# POWER.net
KiCad netlist of a schematic drawn in Altium Designer
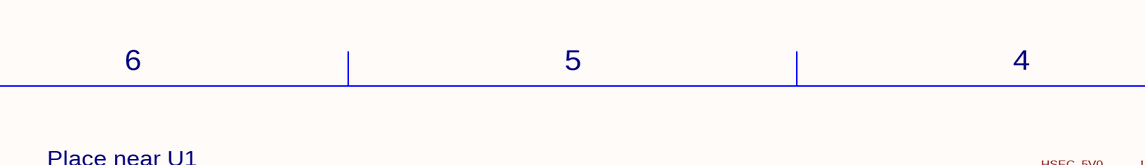
[diagram p0: POWER.SchDoc, top left]
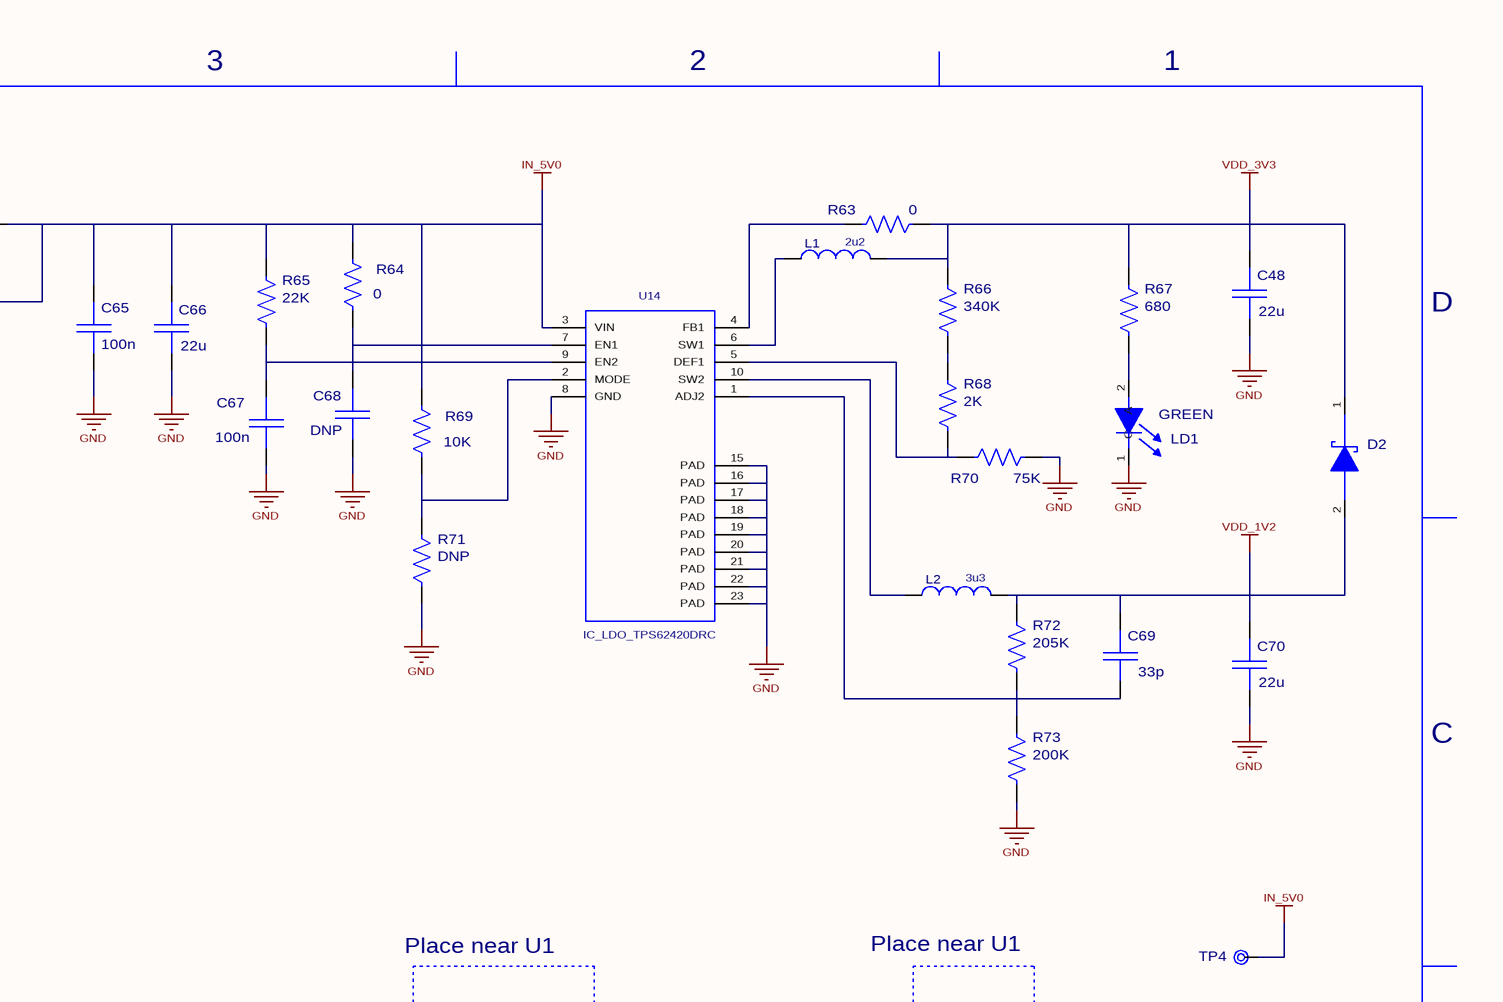
[diagram p1: POWER.SchDoc, top right]
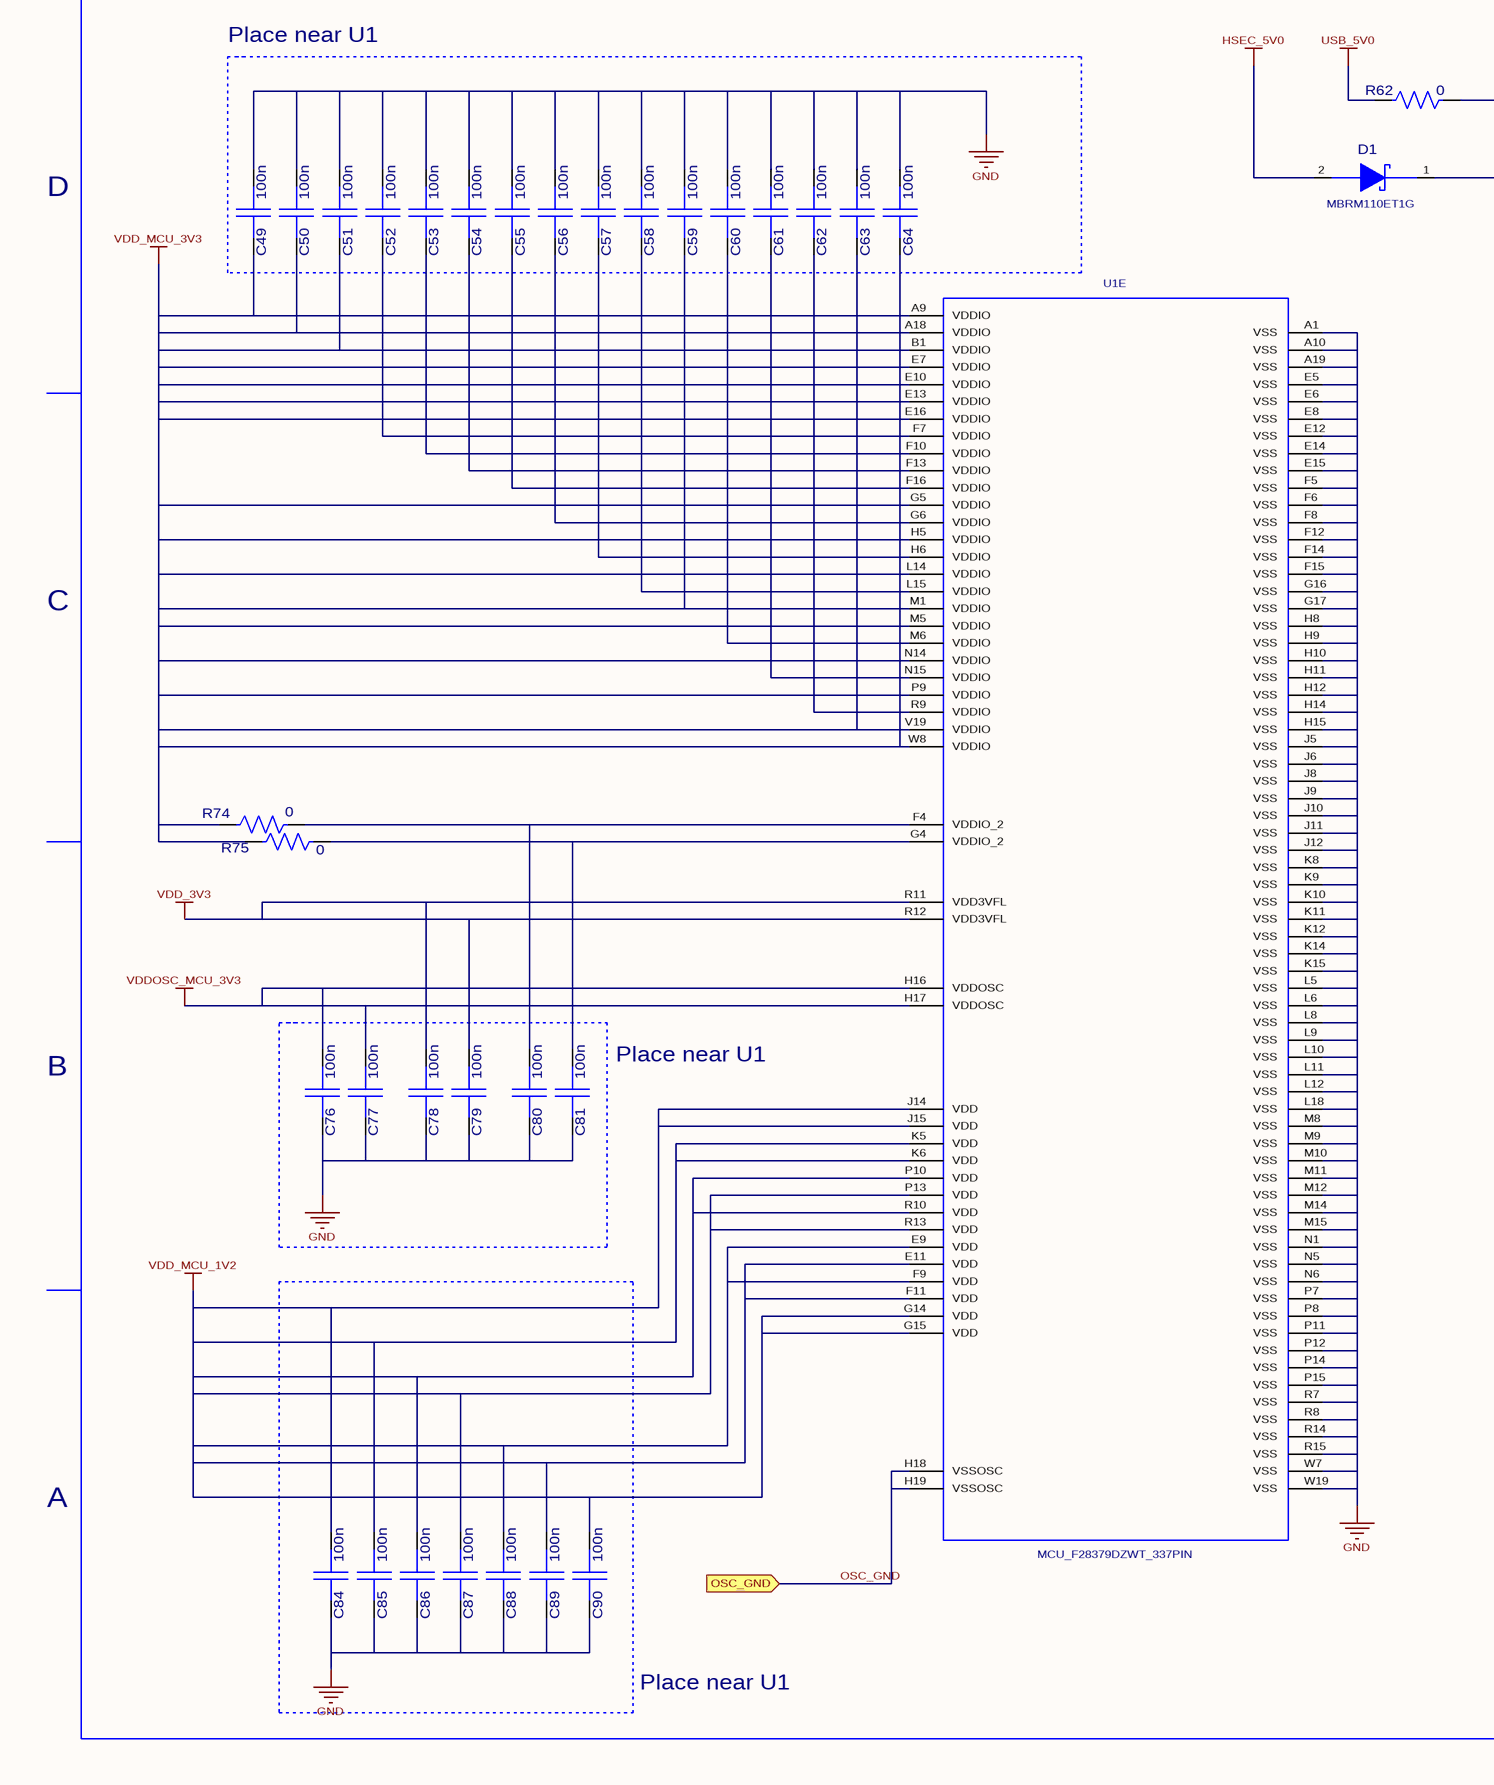
[diagram p2: POWER.SchDoc, bottom left]
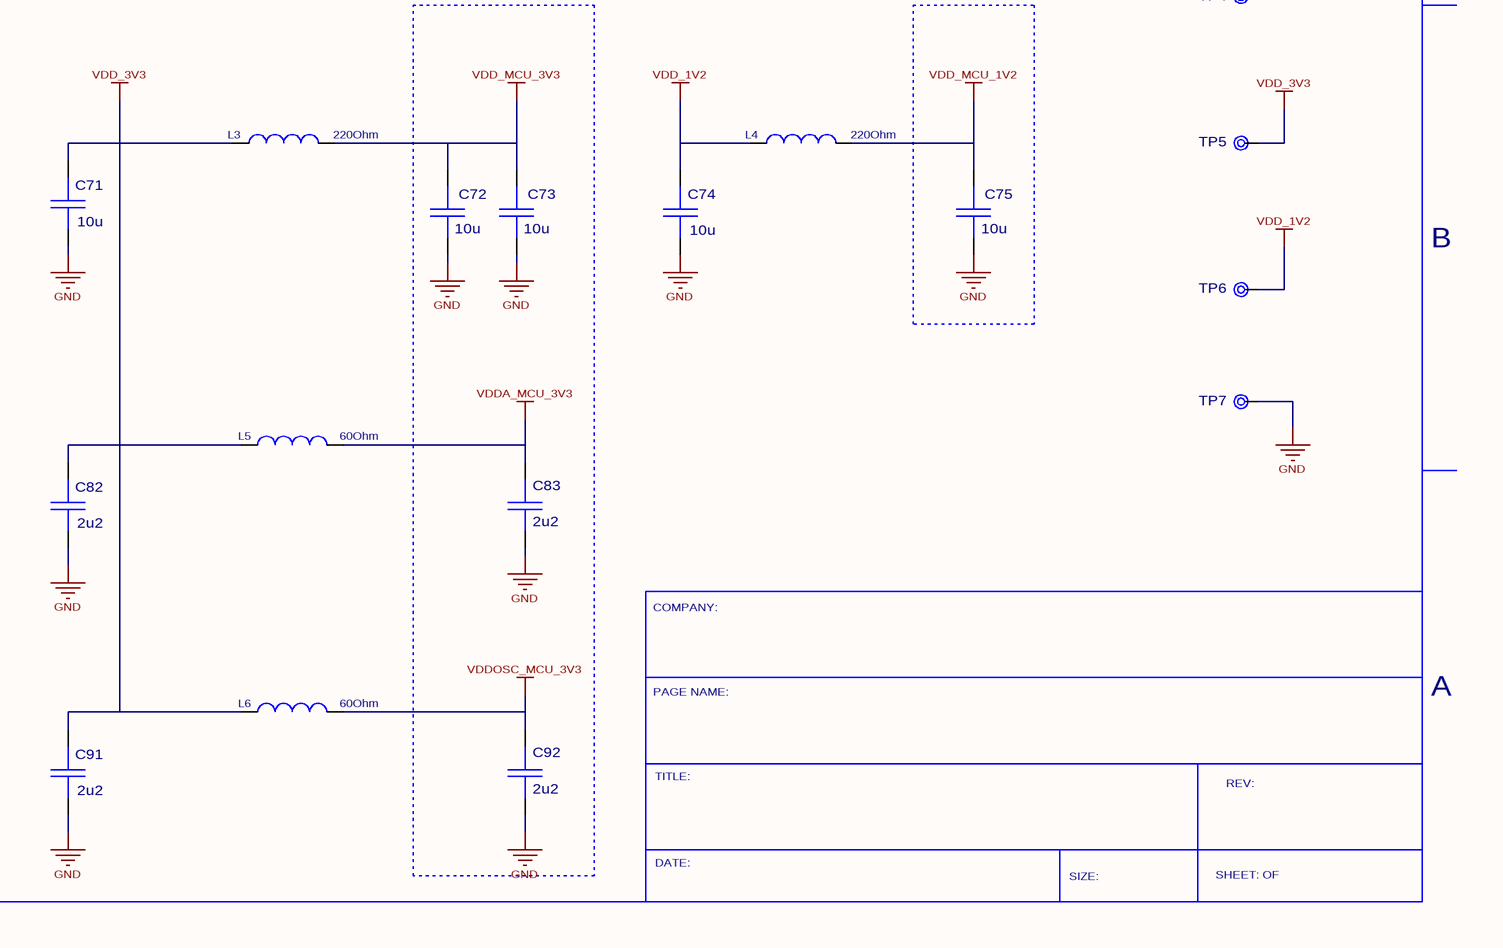
[diagram p3: POWER.SchDoc, bottom right]

(export (version "E")
  (design (tool "Eeschema 10.0.6"))
  (components
    (comp (ref "C48")
      (value "22u")
      (footprint "C0805")
      (description "CAP CER 6.3V 20% X5R 0805")
      (fields (field (name "Comment") "C0805_16V_X7R"))
      (libsource (lib "*") (part "C0805_16V_X7R"))
    )
    (comp (ref "C49")
      (value "100n")
      (footprint "C0402")
      (description "CAP CER 16V 10% X7R 0402")
      (fields (field (name "Comment") "C0402_16V_X7R"))
      (libsource (lib "*") (part "C0402_16V_X7R"))
    )
    (comp (ref "C50")
      (value "100n")
      (footprint "C0402")
      (description "CAP CER 16V 10% X7R 0402")
      (fields (field (name "Comment") "C0402_16V_X7R"))
      (libsource (lib "*") (part "C0402_16V_X7R"))
    )
    (comp (ref "C51")
      (value "100n")
      (footprint "C0402")
      (description "CAP CER 16V 10% X7R 0402")
      (fields (field (name "Comment") "C0402_16V_X7R"))
      (libsource (lib "*") (part "C0402_16V_X7R"))
    )
    (comp (ref "C52")
      (value "100n")
      (footprint "C0402")
      (description "CAP CER 16V 10% X7R 0402")
      (fields (field (name "Comment") "C0402_16V_X7R"))
      (libsource (lib "*") (part "C0402_16V_X7R"))
    )
    (comp (ref "C53")
      (value "100n")
      (footprint "C0402")
      (description "CAP CER 16V 10% X7R 0402")
      (fields (field (name "Comment") "C0402_16V_X7R"))
      (libsource (lib "*") (part "C0402_16V_X7R"))
    )
    (comp (ref "C54")
      (value "100n")
      (footprint "C0402")
      (description "CAP CER 16V 10% X7R 0402")
      (fields (field (name "Comment") "C0402_16V_X7R"))
      (libsource (lib "*") (part "C0402_16V_X7R"))
    )
    (comp (ref "C55")
      (value "100n")
      (footprint "C0402")
      (description "CAP CER 16V 10% X7R 0402")
      (fields (field (name "Comment") "C0402_16V_X7R"))
      (libsource (lib "*") (part "C0402_16V_X7R"))
    )
    (comp (ref "C56")
      (value "100n")
      (footprint "C0402")
      (description "CAP CER 16V 10% X7R 0402")
      (fields (field (name "Comment") "C0402_16V_X7R"))
      (libsource (lib "*") (part "C0402_16V_X7R"))
    )
    (comp (ref "C57")
      (value "100n")
      (footprint "C0402")
      (description "CAP CER 16V 10% X7R 0402")
      (fields (field (name "Comment") "C0402_16V_X7R"))
      (libsource (lib "*") (part "C0402_16V_X7R"))
    )
    (comp (ref "C58")
      (value "100n")
      (footprint "C0402")
      (description "CAP CER 16V 10% X7R 0402")
      (fields (field (name "Comment") "C0402_16V_X7R"))
      (libsource (lib "*") (part "C0402_16V_X7R"))
    )
    (comp (ref "C59")
      (value "100n")
      (footprint "C0402")
      (description "CAP CER 16V 10% X7R 0402")
      (fields (field (name "Comment") "C0402_16V_X7R"))
      (libsource (lib "*") (part "C0402_16V_X7R"))
    )
    (comp (ref "C60")
      (value "100n")
      (footprint "C0402")
      (description "CAP CER 16V 10% X7R 0402")
      (fields (field (name "Comment") "C0402_16V_X7R"))
      (libsource (lib "*") (part "C0402_16V_X7R"))
    )
    (comp (ref "C61")
      (value "100n")
      (footprint "C0402")
      (description "CAP CER 16V 10% X7R 0402")
      (fields (field (name "Comment") "C0402_16V_X7R"))
      (libsource (lib "*") (part "C0402_16V_X7R"))
    )
    (comp (ref "C62")
      (value "100n")
      (footprint "C0402")
      (description "CAP CER 16V 10% X7R 0402")
      (fields (field (name "Comment") "C0402_16V_X7R"))
      (libsource (lib "*") (part "C0402_16V_X7R"))
    )
    (comp (ref "C63")
      (value "100n")
      (footprint "C0402")
      (description "CAP CER 16V 10% X7R 0402")
      (fields (field (name "Comment") "C0402_16V_X7R"))
      (libsource (lib "*") (part "C0402_16V_X7R"))
    )
    (comp (ref "C64")
      (value "100n")
      (footprint "C0402")
      (description "CAP CER 16V 10% X7R 0402")
      (fields (field (name "Comment") "C0402_16V_X7R"))
      (libsource (lib "*") (part "C0402_16V_X7R"))
    )
    (comp (ref "C65")
      (value "100n")
      (footprint "C0402")
      (description "CAP CER 16V 10% X7R 0402")
      (fields (field (name "Comment") "C0402_16V_X7R"))
      (libsource (lib "*") (part "C0402_16V_X7R"))
    )
    (comp (ref "C66")
      (value "22u")
      (footprint "C0805")
      (description "CAP CER 6.3V 20% X5R 0805")
      (fields (field (name "Comment") "C0805_16V_X7R"))
      (libsource (lib "*") (part "C0805_16V_X7R"))
    )
    (comp (ref "C67")
      (value "100n")
      (footprint "C0402")
      (description "CAP CER 16V 10% X7R 0402")
      (fields (field (name "Comment") "C0402_16V_X7R"))
      (libsource (lib "*") (part "C0402_16V_X7R"))
    )
    (comp (ref "C68")
      (value "DNP")
      (footprint "C0402")
      (description "CAP CER 16V 10% X7R 0402")
      (fields (field (name "Comment") "C0402_16V_X7R"))
      (libsource (lib "*") (part "C0402_16V_X7R"))
    )
    (comp (ref "C69")
      (value "33p")
      (footprint "C0402")
      (description "CAP CER 50V NP0 0402")
      (fields (field (name "Comment") "C0402_50V_NP0"))
      (libsource (lib "*") (part "C0402_50V_NP0"))
    )
    (comp (ref "C70")
      (value "22u")
      (footprint "C0805")
      (description "CAP CER 6.3V 20% X5R 0805")
      (fields (field (name "Comment") "C0805_16V_X7R"))
      (libsource (lib "*") (part "C0805_16V_X7R"))
    )
    (comp (ref "C71")
      (value "10u")
      (footprint "C0805")
      (description "CAP CER 10V 20% X5R 0805")
      (fields (field (name "Comment") "C0805_16V_X7R"))
      (libsource (lib "*") (part "C0805_16V_X7R"))
    )
    (comp (ref "C72")
      (value "10u")
      (footprint "C0603")
      (description "CAP CER 6.3V 20% X5R 0603")
      (fields (field (name "Comment") "C0603_16V_X7R"))
      (libsource (lib "*") (part "C0603_16V_X7R"))
    )
    (comp (ref "C73")
      (value "10u")
      (footprint "C0603")
      (description "CAP CER 6.3V 20% X5R 0603")
      (fields (field (name "Comment") "C0603_16V_X7R"))
      (libsource (lib "*") (part "C0603_16V_X7R"))
    )
    (comp (ref "C74")
      (value "10u")
      (footprint "C0805")
      (description "CAP CER 10V 20% X5R 0805")
      (fields (field (name "Comment") "C0805_16V_X7R"))
      (libsource (lib "*") (part "C0805_16V_X7R"))
    )
    (comp (ref "C75")
      (value "10u")
      (footprint "C0603")
      (description "CAP CER 6.3V 20% X5R 0603")
      (fields (field (name "Comment") "C0603_16V_X7R"))
      (libsource (lib "*") (part "C0603_16V_X7R"))
    )
    (comp (ref "C76")
      (value "100n")
      (footprint "C0402")
      (description "CAP CER 16V 10% X7R 0402")
      (fields (field (name "Comment") "C0402_16V_X7R"))
      (libsource (lib "*") (part "C0402_16V_X7R"))
    )
    (comp (ref "C77")
      (value "100n")
      (footprint "C0402")
      (description "CAP CER 16V 10% X7R 0402")
      (fields (field (name "Comment") "C0402_16V_X7R"))
      (libsource (lib "*") (part "C0402_16V_X7R"))
    )
    (comp (ref "C78")
      (value "100n")
      (footprint "C0402")
      (description "CAP CER 16V 10% X7R 0402")
      (fields (field (name "Comment") "C0402_16V_X7R"))
      (libsource (lib "*") (part "C0402_16V_X7R"))
    )
    (comp (ref "C79")
      (value "100n")
      (footprint "C0402")
      (description "CAP CER 16V 10% X7R 0402")
      (fields (field (name "Comment") "C0402_16V_X7R"))
      (libsource (lib "*") (part "C0402_16V_X7R"))
    )
    (comp (ref "C80")
      (value "100n")
      (footprint "C0402")
      (description "CAP CER 16V 10% X7R 0402")
      (fields (field (name "Comment") "C0402_16V_X7R"))
      (libsource (lib "*") (part "C0402_16V_X7R"))
    )
    (comp (ref "C81")
      (value "100n")
      (footprint "C0402")
      (description "CAP CER 16V 10% X7R 0402")
      (fields (field (name "Comment") "C0402_16V_X7R"))
      (libsource (lib "*") (part "C0402_16V_X7R"))
    )
    (comp (ref "C82")
      (value "2u2")
      (footprint "C0805")
      (description "CAP CER 10V 20% X5R 0805")
      (fields (field (name "Comment") "C0805_16V_X7R"))
      (libsource (lib "*") (part "C0805_16V_X7R"))
    )
    (comp (ref "C83")
      (value "2u2")
      (footprint "C0603")
      (description "CAP CER 10V 20% X5R 0603")
      (fields (field (name "Comment") "C0603_16V_X7R"))
      (libsource (lib "*") (part "C0603_16V_X7R"))
    )
    (comp (ref "C84")
      (value "100n")
      (footprint "C0402")
      (description "CAP CER 16V 10% X7R 0402")
      (fields (field (name "Comment") "C0402_16V_X7R"))
      (libsource (lib "*") (part "C0402_16V_X7R"))
    )
    (comp (ref "C85")
      (value "100n")
      (footprint "C0402")
      (description "CAP CER 16V 10% X7R 0402")
      (fields (field (name "Comment") "C0402_16V_X7R"))
      (libsource (lib "*") (part "C0402_16V_X7R"))
    )
    (comp (ref "C86")
      (value "100n")
      (footprint "C0402")
      (description "CAP CER 16V 10% X7R 0402")
      (fields (field (name "Comment") "C0402_16V_X7R"))
      (libsource (lib "*") (part "C0402_16V_X7R"))
    )
    (comp (ref "C87")
      (value "100n")
      (footprint "C0402")
      (description "CAP CER 16V 10% X7R 0402")
      (fields (field (name "Comment") "C0402_16V_X7R"))
      (libsource (lib "*") (part "C0402_16V_X7R"))
    )
    (comp (ref "C88")
      (value "100n")
      (footprint "C0402")
      (description "CAP CER 16V 10% X7R 0402")
      (fields (field (name "Comment") "C0402_16V_X7R"))
      (libsource (lib "*") (part "C0402_16V_X7R"))
    )
    (comp (ref "C89")
      (value "100n")
      (footprint "C0402")
      (description "CAP CER 16V 10% X7R 0402")
      (fields (field (name "Comment") "C0402_16V_X7R"))
      (libsource (lib "*") (part "C0402_16V_X7R"))
    )
    (comp (ref "C90")
      (value "100n")
      (footprint "C0402")
      (description "CAP CER 16V 10% X7R 0402")
      (fields (field (name "Comment") "C0402_16V_X7R"))
      (libsource (lib "*") (part "C0402_16V_X7R"))
    )
    (comp (ref "C91")
      (value "2u2")
      (footprint "C0805")
      (description "CAP CER 10V 20% X5R 0805")
      (fields (field (name "Comment") "C0805_16V_X7R"))
      (libsource (lib "*") (part "C0805_16V_X7R"))
    )
    (comp (ref "C92")
      (value "2u2")
      (footprint "C0603")
      (description "CAP CER 10V 20% X5R 0603")
      (fields (field (name "Comment") "C0603_16V_X7R"))
      (libsource (lib "*") (part "C0603_16V_X7R"))
    )
    (comp (ref "D1")
      (value "DIODE_SCHOTTKY_MBRM110ET1G")
      (footprint "DO-216AA")
      (description "DIODE SCHOTTKY 10V 1A POWERMITE")
      (fields (field (name "PART NUMBER") "MBRM110ET1G") (field (name "MANUFACTURER") "On Semiconductor"))
      (libsource (lib "*") (part "DIODE_SCHOTTKY_MBRM110ET1G"))
    )
    (comp (ref "D2")
      (value "DIODE_SCHOTTKY_CFSH05-20L")
      (footprint "SOD882L")
      (description "DIODE SCHOTTKY, 220mV@10mA, SOD882L")
      (fields
        (field (name "MANUFACTURER") "Central Semiconductor Corp")
        (field (name "PART NUMBER") "CFSH05-20L TR")
      )
      (libsource (lib "*") (part "DIODE_SCHOTTKY_CFSH05-20L"))
    )
    (comp (ref "L1")
      (value "2u2")
      (footprint "IND_SMD_VLF3010A_COILS")
      (description "Inductor Power 2.2uH 1.0A SMD 20%")
      (fields
        (field (name "MANUFACTURER") "TDK Corporation")
        (field (name "PART NUMBER") "VLF3010AT-2R2M1R0")
      )
      (libsource (lib "*") (part "IND_VLF3010AT-2R2M1R0"))
    )
    (comp (ref "L2")
      (value "3u3")
      (footprint "IND_SMD_VLF3010A_COILS")
      (description "Inductor Power 3.3uH 0.87A SMD 20%")
      (fields
        (field (name "MANUFACTURER") "TDK Corporation")
        (field (name "PART NUMBER") "VLF3010AT-3R3MR87")
      )
      (libsource (lib "*") (part "IND_VLF3010AT-3R3MR87"))
    )
    (comp (ref "L3")
      (value "220Ohm")
      (footprint "L0805")
      (description "FERRITE 2A 220OHM@100MHz 0805 SMD")
      (fields (field (name "PART NUMBER") "BLM21PG221SN1D") (field (name "Comment") "L0805_BLM21PG221SN1D"))
      (libsource (lib "*") (part "L0805_BLM21PG221SN1D"))
    )
    (comp (ref "L4")
      (value "220Ohm")
      (footprint "L0805")
      (description "FERRITE 2A 220OHM@100MHz 0805 SMD")
      (fields (field (name "PART NUMBER") "BLM21PG221SN1D") (field (name "Comment") "L0805_BLM21PG221SN1D"))
      (libsource (lib "*") (part "L0805_BLM21PG221SN1D"))
    )
    (comp (ref "L5")
      (value "60Ohm")
      (footprint "L0805")
      (description "FERRITE 3A 60OHM@100MHz 0805 SMD")
      (fields (field (name "PART NUMBER") "BKP2125HS600-T") (field (name "Comment") "L0805_BKP2125HS600-T"))
      (libsource (lib "*") (part "L0805_BKP2125HS600-T"))
    )
    (comp (ref "L6")
      (value "60Ohm")
      (footprint "L0805")
      (description "FERRITE 3A 60OHM@100MHz 0805 SMD")
      (fields (field (name "PART NUMBER") "BKP2125HS600-T") (field (name "Comment") "L0805_BKP2125HS600-T"))
      (libsource (lib "*") (part "L0805_BKP2125HS600-T"))
    )
    (comp (ref "LD1")
      (value "GREEN")
      (footprint "LED0805")
      (description "LED GREEN 0805 SMD, Diffused, 567nm")
      (fields (field (name "Comment") "LED0805_GREEN"))
      (libsource (lib "*") (part "LED0805_GREEN"))
    )
    (comp (ref "R62")
      (value "0")
      (footprint "R0805")
      (description "RES 1/8W 5% 0805 SMD")
      (fields (field (name "Comment") "R0805_5%"))
      (libsource (lib "*") (part "R0805_5%"))
    )
    (comp (ref "R63")
      (value "0")
      (footprint "R0402")
      (description "RES 1/16W 5% 0402 SMD")
      (fields (field (name "Comment") "R0402_5%"))
      (libsource (lib "*") (part "R0402_5%"))
    )
    (comp (ref "R64")
      (value "0")
      (footprint "R0402")
      (description "RES 1/16W 5% 0402 SMD")
      (fields (field (name "Comment") "R0402_5%"))
      (libsource (lib "*") (part "R0402_5%"))
    )
    (comp (ref "R65")
      (value "22K")
      (footprint "R0402")
      (description "RES 1/16W 1% 0402 SMD")
      (fields (field (name "Comment") "R0402_1%"))
      (libsource (lib "*") (part "R0402_1%"))
    )
    (comp (ref "R66")
      (value "340K")
      (footprint "R0402")
      (description "RES 1/16W 1% 0402 SMD")
      (fields (field (name "Comment") "R0402_1%"))
      (libsource (lib "*") (part "R0402_1%"))
    )
    (comp (ref "R67")
      (value "680")
      (footprint "R0402")
      (description "RES 1/16W 5% 0402 SMD")
      (fields (field (name "Comment") "R0402_5%"))
      (libsource (lib "*") (part "R0402_5%"))
    )
    (comp (ref "R68")
      (value "2K")
      (footprint "R0402")
      (description "RES 1/16W 1% 0402 SMD")
      (fields (field (name "Comment") "R0402_1%"))
      (libsource (lib "*") (part "R0402_1%"))
    )
    (comp (ref "R69")
      (value "10K")
      (footprint "R0402")
      (description "RES 1/16W 5% 0402 SMD")
      (fields (field (name "Comment") "R0402_5%"))
      (libsource (lib "*") (part "R0402_5%"))
    )
    (comp (ref "R70")
      (value "75K")
      (footprint "R0402")
      (description "RES 1/16W 0.5% 0402 SMD")
      (fields (field (name "Comment") "R0402_1%"))
      (libsource (lib "*") (part "R0402_1%"))
    )
    (comp (ref "R71")
      (value "DNP")
      (footprint "R0603")
      (description "RES 1/10W 5% 0603 SMD")
      (fields (field (name "Comment") "R0603_5%"))
      (libsource (lib "") (part "R0603_5%_1"))
    )
    (comp (ref "R72")
      (value "205K")
      (footprint "R0402")
      (description "RES 1/16W 1% 0402 SMD")
      (fields (field (name "Comment") "R0402_1%"))
      (libsource (lib "*") (part "R0402_1%"))
    )
    (comp (ref "R73")
      (value "200K")
      (footprint "R0402")
      (description "RES 1/16W 0.5% 0402 SMD")
      (fields (field (name "Comment") "R0402_1%"))
      (libsource (lib "*") (part "R0402_1%"))
    )
    (comp (ref "R74")
      (value "0")
      (footprint "R0603")
      (description "RES 1/10W 5% 0603 SMD")
      (fields (field (name "Comment") "R0603_5%"))
      (libsource (lib "*") (part "R0603_5%"))
    )
    (comp (ref "R75")
      (value "0")
      (footprint "R0603")
      (description "RES 1/10W 5% 0603 SMD")
      (fields (field (name "Comment") "R0603_5%"))
      (libsource (lib "*") (part "R0603_5%"))
    )
    (comp (ref "TP4")
      (value "VIA_20_40")
      (footprint "VIA_20_40")
      (description "Via, 20 ID, 40 OD (mil)")
      (libsource (lib "*") (part "VIA_20_40"))
    )
    (comp (ref "TP5")
      (value "VIA_20_40")
      (footprint "VIA_20_40")
      (description "Via, 20 ID, 40 OD (mil)")
      (libsource (lib "*") (part "VIA_20_40"))
    )
    (comp (ref "TP6")
      (value "VIA_20_40")
      (footprint "VIA_20_40")
      (description "Via, 20 ID, 40 OD (mil)")
      (libsource (lib "*") (part "VIA_20_40"))
    )
    (comp (ref "TP7")
      (value "VIA_20_40")
      (footprint "VIA_20_40")
      (description "Via, 20 ID, 40 OD (mil)")
      (libsource (lib "*") (part "VIA_20_40"))
    )
    (comp (ref "U1")
      (value "MCU_F28379DZWT_337PIN")
      (footprint "TI_ZWT_337BGA")
      (description "MCU F2837x 337pin ZWT BGA")
      (fields (field (name "PART NUMBER") "TMS320F28379DZWT"))
      (libsource (lib "*") (part "MCU_F28379DZWT_337PIN"))
    )
    (comp (ref "U14")
      (value "IC_LDO_TPS62420DRC")
      (footprint "TI_DRC_10")
      (description "IC Dual Step Down Converter, 2.25MHz, 600mA/1A")
      (fields (field (name "PART NUMBER") "TPS62420DRC"))
      (libsource (lib "*") (part "IC_LDO_TPS62420DRC"))
    )
  )
  (nets
    (net (code "1") (name "/OSC_GND") (class "Default")
      (node (ref "U1") (pin "H18") (pinfunction "VSSOSC_H18") (pintype "passive"))
      (node (ref "U1") (pin "H19") (pinfunction "VSSOSC_H19") (pintype "passive"))
    )
    (net (code "2") (name "GND") (class "Default")
      (node (ref "C48") (pin "1") (pinfunction "1_1") (pintype "passive"))
      (node (ref "C49") (pin "2") (pinfunction "2_2") (pintype "passive"))
      (node (ref "C50") (pin "2") (pinfunction "2_2") (pintype "passive"))
      (node (ref "C51") (pin "2") (pinfunction "2_2") (pintype "passive"))
      (node (ref "C52") (pin "2") (pinfunction "2_2") (pintype "passive"))
      (node (ref "C53") (pin "2") (pinfunction "2_2") (pintype "passive"))
      (node (ref "C54") (pin "2") (pinfunction "2_2") (pintype "passive"))
      (node (ref "C55") (pin "2") (pinfunction "2_2") (pintype "passive"))
      (node (ref "C56") (pin "2") (pinfunction "2_2") (pintype "passive"))
      (node (ref "C57") (pin "2") (pinfunction "2_2") (pintype "passive"))
      (node (ref "C58") (pin "2") (pinfunction "2_2") (pintype "passive"))
      (node (ref "C59") (pin "2") (pinfunction "2_2") (pintype "passive"))
      (node (ref "C60") (pin "2") (pinfunction "2_2") (pintype "passive"))
      (node (ref "C61") (pin "2") (pinfunction "2_2") (pintype "passive"))
      (node (ref "C62") (pin "2") (pinfunction "2_2") (pintype "passive"))
      (node (ref "C63") (pin "2") (pinfunction "2_2") (pintype "passive"))
      (node (ref "C64") (pin "2") (pinfunction "2_2") (pintype "passive"))
      (node (ref "C65") (pin "1") (pinfunction "1_1") (pintype "passive"))
      (node (ref "C66") (pin "1") (pinfunction "1_1") (pintype "passive"))
      (node (ref "C67") (pin "1") (pinfunction "1_1") (pintype "passive"))
      (node (ref "C68") (pin "1") (pinfunction "1_1") (pintype "passive"))
      (node (ref "C70") (pin "1") (pinfunction "1_1") (pintype "passive"))
      (node (ref "C71") (pin "1") (pinfunction "1_1") (pintype "passive"))
      (node (ref "C72") (pin "1") (pinfunction "1_1") (pintype "passive"))
      (node (ref "C73") (pin "1") (pinfunction "1_1") (pintype "passive"))
      (node (ref "C74") (pin "1") (pinfunction "1_1") (pintype "passive"))
      (node (ref "C75") (pin "1") (pinfunction "1_1") (pintype "passive"))
      (node (ref "C76") (pin "1") (pinfunction "1_1") (pintype "passive"))
      (node (ref "C77") (pin "1") (pinfunction "1_1") (pintype "passive"))
      (node (ref "C78") (pin "1") (pinfunction "1_1") (pintype "passive"))
      (node (ref "C79") (pin "1") (pinfunction "1_1") (pintype "passive"))
      (node (ref "C80") (pin "1") (pinfunction "1_1") (pintype "passive"))
      (node (ref "C81") (pin "1") (pinfunction "1_1") (pintype "passive"))
      (node (ref "C82") (pin "1") (pinfunction "1_1") (pintype "passive"))
      (node (ref "C83") (pin "1") (pinfunction "1_1") (pintype "passive"))
      (node (ref "C84") (pin "1") (pinfunction "1_1") (pintype "passive"))
      (node (ref "C85") (pin "1") (pinfunction "1_1") (pintype "passive"))
      (node (ref "C86") (pin "1") (pinfunction "1_1") (pintype "passive"))
      (node (ref "C87") (pin "1") (pinfunction "1_1") (pintype "passive"))
      (node (ref "C88") (pin "1") (pinfunction "1_1") (pintype "passive"))
      (node (ref "C89") (pin "1") (pinfunction "1_1") (pintype "passive"))
      (node (ref "C90") (pin "1") (pinfunction "1_1") (pintype "passive"))
      (node (ref "C91") (pin "1") (pinfunction "1_1") (pintype "passive"))
      (node (ref "C92") (pin "1") (pinfunction "1_1") (pintype "passive"))
      (node (ref "LD1") (pin "1") (pinfunction "C_1") (pintype "passive"))
      (node (ref "R70") (pin "2") (pinfunction "2_2") (pintype "passive"))
      (node (ref "R71") (pin "2") (pinfunction "2_2") (pintype "passive"))
      (node (ref "R73") (pin "2") (pinfunction "2_2") (pintype "passive"))
      (node (ref "TP7") (pin "1") (pinfunction "1_1") (pintype "passive"))
      (node (ref "U1") (pin "A1") (pinfunction "VSS_A1") (pintype "passive"))
      (node (ref "U1") (pin "A10") (pinfunction "VSS_A10") (pintype "passive"))
      (node (ref "U1") (pin "A19") (pinfunction "VSS_A19") (pintype "passive"))
      (node (ref "U1") (pin "E12") (pinfunction "VSS_E12") (pintype "passive"))
      (node (ref "U1") (pin "E14") (pinfunction "VSS_E14") (pintype "passive"))
      (node (ref "U1") (pin "E15") (pinfunction "VSS_E15") (pintype "passive"))
      (node (ref "U1") (pin "E5") (pinfunction "VSS_E5") (pintype "passive"))
      (node (ref "U1") (pin "E6") (pinfunction "VSS_E6") (pintype "passive"))
      (node (ref "U1") (pin "E8") (pinfunction "VSS_E8") (pintype "passive"))
      (node (ref "U1") (pin "F12") (pinfunction "VSS_F12") (pintype "passive"))
      (node (ref "U1") (pin "F14") (pinfunction "VSS_F14") (pintype "passive"))
      (node (ref "U1") (pin "F15") (pinfunction "VSS_F15") (pintype "passive"))
      (node (ref "U1") (pin "F5") (pinfunction "VSS_F5") (pintype "passive"))
      (node (ref "U1") (pin "F6") (pinfunction "VSS_F6") (pintype "passive"))
      (node (ref "U1") (pin "F8") (pinfunction "VSS_F8") (pintype "passive"))
      (node (ref "U1") (pin "G16") (pinfunction "VSS_G16") (pintype "passive"))
      (node (ref "U1") (pin "G17") (pinfunction "VSS_G17") (pintype "passive"))
      (node (ref "U1") (pin "H10") (pinfunction "VSS_H10") (pintype "passive"))
      (node (ref "U1") (pin "H11") (pinfunction "VSS_H11") (pintype "passive"))
      (node (ref "U1") (pin "H12") (pinfunction "VSS_H12") (pintype "passive"))
      (node (ref "U1") (pin "H14") (pinfunction "VSS_H14") (pintype "passive"))
      (node (ref "U1") (pin "H15") (pinfunction "VSS_H15") (pintype "passive"))
      (node (ref "U1") (pin "H8") (pinfunction "VSS_H8") (pintype "passive"))
      (node (ref "U1") (pin "H9") (pinfunction "VSS_H9") (pintype "passive"))
      (node (ref "U1") (pin "J10") (pinfunction "VSS_J10") (pintype "passive"))
      (node (ref "U1") (pin "J11") (pinfunction "VSS_J11") (pintype "passive"))
      (node (ref "U1") (pin "J12") (pinfunction "VSS_J12") (pintype "passive"))
      (node (ref "U1") (pin "J5") (pinfunction "VSS_J5") (pintype "passive"))
      (node (ref "U1") (pin "J6") (pinfunction "VSS_J6") (pintype "passive"))
      (node (ref "U1") (pin "J8") (pinfunction "VSS_J8") (pintype "passive"))
      (node (ref "U1") (pin "J9") (pinfunction "VSS_J9") (pintype "passive"))
      (node (ref "U1") (pin "K10") (pinfunction "VSS_K10") (pintype "passive"))
      (node (ref "U1") (pin "K11") (pinfunction "VSS_K11") (pintype "passive"))
      (node (ref "U1") (pin "K12") (pinfunction "VSS_K12") (pintype "passive"))
      (node (ref "U1") (pin "K14") (pinfunction "VSS_K14") (pintype "passive"))
      (node (ref "U1") (pin "K15") (pinfunction "VSS_K15") (pintype "passive"))
      (node (ref "U1") (pin "K8") (pinfunction "VSS_K8") (pintype "passive"))
      (node (ref "U1") (pin "K9") (pinfunction "VSS_K9") (pintype "passive"))
      (node (ref "U1") (pin "L10") (pinfunction "VSS_L10") (pintype "passive"))
      (node (ref "U1") (pin "L11") (pinfunction "VSS_L11") (pintype "passive"))
      (node (ref "U1") (pin "L12") (pinfunction "VSS_L12") (pintype "passive"))
      (node (ref "U1") (pin "L18") (pinfunction "VSS_L18") (pintype "passive"))
      (node (ref "U1") (pin "L5") (pinfunction "VSS_L5") (pintype "passive"))
      (node (ref "U1") (pin "L6") (pinfunction "VSS_L6") (pintype "passive"))
      (node (ref "U1") (pin "L8") (pinfunction "VSS_L8") (pintype "passive"))
      (node (ref "U1") (pin "L9") (pinfunction "VSS_L9") (pintype "passive"))
      (node (ref "U1") (pin "M10") (pinfunction "VSS_M10") (pintype "passive"))
      (node (ref "U1") (pin "M11") (pinfunction "VSS_M11") (pintype "passive"))
      (node (ref "U1") (pin "M12") (pinfunction "VSS_M12") (pintype "passive"))
      (node (ref "U1") (pin "M14") (pinfunction "VSS_M14") (pintype "passive"))
      (node (ref "U1") (pin "M15") (pinfunction "VSS_M15") (pintype "passive"))
      (node (ref "U1") (pin "M8") (pinfunction "VSS_M8") (pintype "passive"))
      (node (ref "U1") (pin "M9") (pinfunction "VSS_M9") (pintype "passive"))
      (node (ref "U1") (pin "N1") (pinfunction "VSS_N1") (pintype "passive"))
      (node (ref "U1") (pin "N5") (pinfunction "VSS_N5") (pintype "passive"))
      (node (ref "U1") (pin "N6") (pinfunction "VSS_N6") (pintype "passive"))
      (node (ref "U1") (pin "P11") (pinfunction "VSS_P11") (pintype "passive"))
      (node (ref "U1") (pin "P12") (pinfunction "VSS_P12") (pintype "passive"))
      (node (ref "U1") (pin "P14") (pinfunction "VSS_P14") (pintype "passive"))
      (node (ref "U1") (pin "P15") (pinfunction "VSS_P15") (pintype "passive"))
      (node (ref "U1") (pin "P7") (pinfunction "VSS_P7") (pintype "passive"))
      (node (ref "U1") (pin "P8") (pinfunction "VSS_P8") (pintype "passive"))
      (node (ref "U1") (pin "R14") (pinfunction "VSS_R14") (pintype "passive"))
      (node (ref "U1") (pin "R15") (pinfunction "VSS_R15") (pintype "passive"))
      (node (ref "U1") (pin "R7") (pinfunction "VSS_R7") (pintype "passive"))
      (node (ref "U1") (pin "R8") (pinfunction "VSS_R8") (pintype "passive"))
      (node (ref "U1") (pin "W19") (pinfunction "VSS_W19") (pintype "passive"))
      (node (ref "U1") (pin "W7") (pinfunction "VSS_W7") (pintype "passive"))
      (node (ref "U14") (pin "15") (pinfunction "PAD_15") (pintype "passive"))
      (node (ref "U14") (pin "16") (pinfunction "PAD_16") (pintype "passive"))
      (node (ref "U14") (pin "17") (pinfunction "PAD_17") (pintype "passive"))
      (node (ref "U14") (pin "18") (pinfunction "PAD_18") (pintype "passive"))
      (node (ref "U14") (pin "19") (pinfunction "PAD_19") (pintype "passive"))
      (node (ref "U14") (pin "20") (pinfunction "PAD_20") (pintype "passive"))
      (node (ref "U14") (pin "21") (pinfunction "PAD_21") (pintype "passive"))
      (node (ref "U14") (pin "22") (pinfunction "PAD_22") (pintype "passive"))
      (node (ref "U14") (pin "23") (pinfunction "PAD_23") (pintype "passive"))
      (node (ref "U14") (pin "8") (pinfunction "GND_8") (pintype "passive"))
    )
    (net (code "3") (name "HSEC_5V0") (class "Default")
      (node (ref "D1") (pin "2") (pinfunction "A_2") (pintype "passive"))
    )
    (net (code "4") (name "IN_5V0") (class "Default")
      (node (ref "C65") (pin "2") (pinfunction "2_2") (pintype "passive"))
      (node (ref "C66") (pin "2") (pinfunction "2_2") (pintype "passive"))
      (node (ref "D1") (pin "1") (pinfunction "C_1") (pintype "passive"))
      (node (ref "R62") (pin "2") (pinfunction "2_2") (pintype "passive"))
      (node (ref "R64") (pin "2") (pinfunction "2_2") (pintype "passive"))
      (node (ref "R65") (pin "1") (pinfunction "1_1") (pintype "passive"))
      (node (ref "R69") (pin "2") (pinfunction "2_2") (pintype "passive"))
      (node (ref "TP4") (pin "1") (pinfunction "1_1") (pintype "passive"))
      (node (ref "U14") (pin "3") (pinfunction "VIN_3") (pintype "passive"))
    )
    (net (code "5") (name "Net-(C80-Pad2)") (class "Default")
      (node (ref "C80") (pin "2") (pinfunction "2_2") (pintype "passive"))
      (node (ref "R74") (pin "2") (pinfunction "2_2") (pintype "passive"))
      (node (ref "U1") (pin "F4") (pinfunction "VDDIO_2_F4") (pintype "power_in"))
    )
    (net (code "6") (name "Net-(C81-Pad2)") (class "Default")
      (node (ref "C81") (pin "2") (pinfunction "2_2") (pintype "passive"))
      (node (ref "R75") (pin "2") (pinfunction "2_2") (pintype "passive"))
      (node (ref "U1") (pin "G4") (pinfunction "VDDIO_2_G4") (pintype "power_in"))
    )
    (net (code "7") (name "Net-(LD1-A)") (class "Default")
      (node (ref "LD1") (pin "2") (pinfunction "A_2") (pintype "passive"))
      (node (ref "R67") (pin "2") (pinfunction "2_2") (pintype "passive"))
    )
    (net (code "8") (name "Net-(R66-Pad2)") (class "Default")
      (node (ref "R66") (pin "2") (pinfunction "2_2") (pintype "passive"))
      (node (ref "R68") (pin "1") (pinfunction "1_1") (pintype "passive"))
    )
    (net (code "9") (name "Net-(U14-ADJ2)") (class "Default")
      (node (ref "C69") (pin "1") (pinfunction "1_1") (pintype "passive"))
      (node (ref "R72") (pin "2") (pinfunction "2_2") (pintype "passive"))
      (node (ref "R73") (pin "1") (pinfunction "1_1") (pintype "passive"))
      (node (ref "U14") (pin "1") (pinfunction "ADJ2_1") (pintype "passive"))
    )
    (net (code "10") (name "Net-(U14-DEF1)") (class "Default")
      (node (ref "R68") (pin "2") (pinfunction "2_2") (pintype "passive"))
      (node (ref "R70") (pin "1") (pinfunction "1_1") (pintype "passive"))
      (node (ref "U14") (pin "5") (pinfunction "DEF1_5") (pintype "passive"))
    )
    (net (code "11") (name "Net-(U14-EN1)") (class "Default")
      (node (ref "C68") (pin "2") (pinfunction "2_2") (pintype "passive"))
      (node (ref "R64") (pin "1") (pinfunction "1_1") (pintype "passive"))
      (node (ref "U14") (pin "7") (pinfunction "EN1_7") (pintype "passive"))
    )
    (net (code "12") (name "Net-(U14-EN2)") (class "Default")
      (node (ref "C67") (pin "2") (pinfunction "2_2") (pintype "passive"))
      (node (ref "R65") (pin "2") (pinfunction "2_2") (pintype "passive"))
      (node (ref "U14") (pin "9") (pinfunction "EN2_9") (pintype "passive"))
    )
    (net (code "13") (name "Net-(U14-FB1)") (class "Default")
      (node (ref "R63") (pin "2") (pinfunction "2_2") (pintype "passive"))
      (node (ref "U14") (pin "4") (pinfunction "FB1_4") (pintype "passive"))
    )
    (net (code "14") (name "Net-(U14-MODE)") (class "Default")
      (node (ref "R69") (pin "1") (pinfunction "1_1") (pintype "passive"))
      (node (ref "R71") (pin "1") (pinfunction "1_1") (pintype "passive"))
      (node (ref "U14") (pin "2") (pinfunction "MODE_2") (pintype "passive"))
    )
    (net (code "15") (name "Net-(U14-SW1)") (class "Default")
      (node (ref "L1") (pin "1") (pinfunction "1_1") (pintype "passive"))
      (node (ref "U14") (pin "6") (pinfunction "SW1_6") (pintype "passive"))
    )
    (net (code "16") (name "Net-(U14-SW2)") (class "Default")
      (node (ref "L2") (pin "1") (pinfunction "1_1") (pintype "passive"))
      (node (ref "U14") (pin "10") (pinfunction "SW2_10") (pintype "passive"))
    )
    (net (code "17") (name "USB_5V0") (class "Default")
      (node (ref "R62") (pin "1") (pinfunction "1_1") (pintype "passive"))
    )
    (net (code "18") (name "VDDA_MCU_3V3") (class "Default")
      (node (ref "C83") (pin "2") (pinfunction "2_2") (pintype "passive"))
      (node (ref "L5") (pin "2") (pinfunction "2_2") (pintype "passive"))
    )
    (net (code "19") (name "VDDOSC_MCU_3V3") (class "Default")
      (node (ref "C76") (pin "2") (pinfunction "2_2") (pintype "passive"))
      (node (ref "C77") (pin "2") (pinfunction "2_2") (pintype "passive"))
      (node (ref "C92") (pin "2") (pinfunction "2_2") (pintype "passive"))
      (node (ref "L6") (pin "2") (pinfunction "2_2") (pintype "passive"))
      (node (ref "U1") (pin "H16") (pinfunction "VDDOSC_H16") (pintype "power_in"))
      (node (ref "U1") (pin "H17") (pinfunction "VDDOSC_H17") (pintype "power_in"))
    )
    (net (code "20") (name "VDD_1V2") (class "Default")
      (node (ref "C69") (pin "2") (pinfunction "2_2") (pintype "passive"))
      (node (ref "C70") (pin "2") (pinfunction "2_2") (pintype "passive"))
      (node (ref "C74") (pin "2") (pinfunction "2_2") (pintype "passive"))
      (node (ref "D2") (pin "2") (pinfunction "A_2") (pintype "passive"))
      (node (ref "L2") (pin "2") (pinfunction "2_2") (pintype "passive"))
      (node (ref "L4") (pin "1") (pinfunction "1_1") (pintype "passive"))
      (node (ref "R72") (pin "1") (pinfunction "1_1") (pintype "passive"))
      (node (ref "TP6") (pin "1") (pinfunction "1_1") (pintype "passive"))
    )
    (net (code "21") (name "VDD_3V3") (class "Default")
      (node (ref "C48") (pin "2") (pinfunction "2_2") (pintype "passive"))
      (node (ref "C71") (pin "2") (pinfunction "2_2") (pintype "passive"))
      (node (ref "C78") (pin "2") (pinfunction "2_2") (pintype "passive"))
      (node (ref "C79") (pin "2") (pinfunction "2_2") (pintype "passive"))
      (node (ref "C82") (pin "2") (pinfunction "2_2") (pintype "passive"))
      (node (ref "C91") (pin "2") (pinfunction "2_2") (pintype "passive"))
      (node (ref "D2") (pin "1") (pinfunction "C_1") (pintype "passive"))
      (node (ref "L1") (pin "2") (pinfunction "2_2") (pintype "passive"))
      (node (ref "L3") (pin "1") (pinfunction "1_1") (pintype "passive"))
      (node (ref "L5") (pin "1") (pinfunction "1_1") (pintype "passive"))
      (node (ref "L6") (pin "1") (pinfunction "1_1") (pintype "passive"))
      (node (ref "R63") (pin "1") (pinfunction "1_1") (pintype "passive"))
      (node (ref "R66") (pin "1") (pinfunction "1_1") (pintype "passive"))
      (node (ref "R67") (pin "1") (pinfunction "1_1") (pintype "passive"))
      (node (ref "TP5") (pin "1") (pinfunction "1_1") (pintype "passive"))
      (node (ref "U1") (pin "R11") (pinfunction "VDD3VFL_R11") (pintype "power_in"))
      (node (ref "U1") (pin "R12") (pinfunction "VDD3VFL_R12") (pintype "power_in"))
    )
    (net (code "22") (name "VDD_MCU_1V2") (class "Default")
      (node (ref "C75") (pin "2") (pinfunction "2_2") (pintype "passive"))
      (node (ref "C84") (pin "2") (pinfunction "2_2") (pintype "passive"))
      (node (ref "C85") (pin "2") (pinfunction "2_2") (pintype "passive"))
      (node (ref "C86") (pin "2") (pinfunction "2_2") (pintype "passive"))
      (node (ref "C87") (pin "2") (pinfunction "2_2") (pintype "passive"))
      (node (ref "C88") (pin "2") (pinfunction "2_2") (pintype "passive"))
      (node (ref "C89") (pin "2") (pinfunction "2_2") (pintype "passive"))
      (node (ref "C90") (pin "2") (pinfunction "2_2") (pintype "passive"))
      (node (ref "L4") (pin "2") (pinfunction "2_2") (pintype "passive"))
      (node (ref "U1") (pin "E11") (pinfunction "VDD_E11") (pintype "power_in"))
      (node (ref "U1") (pin "E9") (pinfunction "VDD_E9") (pintype "power_in"))
      (node (ref "U1") (pin "F11") (pinfunction "VDD_F11") (pintype "power_in"))
      (node (ref "U1") (pin "F9") (pinfunction "VDD_F9") (pintype "power_in"))
      (node (ref "U1") (pin "G14") (pinfunction "VDD_G14") (pintype "power_in"))
      (node (ref "U1") (pin "G15") (pinfunction "VDD_G15") (pintype "power_in"))
      (node (ref "U1") (pin "J14") (pinfunction "VDD_J14") (pintype "power_in"))
      (node (ref "U1") (pin "J15") (pinfunction "VDD_J15") (pintype "power_in"))
      (node (ref "U1") (pin "K5") (pinfunction "VDD_K5") (pintype "power_in"))
      (node (ref "U1") (pin "K6") (pinfunction "VDD_K6") (pintype "power_in"))
      (node (ref "U1") (pin "P10") (pinfunction "VDD_P10") (pintype "power_in"))
      (node (ref "U1") (pin "P13") (pinfunction "VDD_P13") (pintype "power_in"))
      (node (ref "U1") (pin "R10") (pinfunction "VDD_R10") (pintype "power_in"))
      (node (ref "U1") (pin "R13") (pinfunction "VDD_R13") (pintype "power_in"))
    )
    (net (code "23") (name "VDD_MCU_3V3") (class "Default")
      (node (ref "C49") (pin "1") (pinfunction "1_1") (pintype "passive"))
      (node (ref "C50") (pin "1") (pinfunction "1_1") (pintype "passive"))
      (node (ref "C51") (pin "1") (pinfunction "1_1") (pintype "passive"))
      (node (ref "C52") (pin "1") (pinfunction "1_1") (pintype "passive"))
      (node (ref "C53") (pin "1") (pinfunction "1_1") (pintype "passive"))
      (node (ref "C54") (pin "1") (pinfunction "1_1") (pintype "passive"))
      (node (ref "C55") (pin "1") (pinfunction "1_1") (pintype "passive"))
      (node (ref "C56") (pin "1") (pinfunction "1_1") (pintype "passive"))
      (node (ref "C57") (pin "1") (pinfunction "1_1") (pintype "passive"))
      (node (ref "C58") (pin "1") (pinfunction "1_1") (pintype "passive"))
      (node (ref "C59") (pin "1") (pinfunction "1_1") (pintype "passive"))
      (node (ref "C60") (pin "1") (pinfunction "1_1") (pintype "passive"))
      (node (ref "C61") (pin "1") (pinfunction "1_1") (pintype "passive"))
      (node (ref "C62") (pin "1") (pinfunction "1_1") (pintype "passive"))
      (node (ref "C63") (pin "1") (pinfunction "1_1") (pintype "passive"))
      (node (ref "C64") (pin "1") (pinfunction "1_1") (pintype "passive"))
      (node (ref "C72") (pin "2") (pinfunction "2_2") (pintype "passive"))
      (node (ref "C73") (pin "2") (pinfunction "2_2") (pintype "passive"))
      (node (ref "L3") (pin "2") (pinfunction "2_2") (pintype "passive"))
      (node (ref "R74") (pin "1") (pinfunction "1_1") (pintype "passive"))
      (node (ref "R75") (pin "1") (pinfunction "1_1") (pintype "passive"))
      (node (ref "U1") (pin "A18") (pinfunction "VDDIO_A18") (pintype "power_in"))
      (node (ref "U1") (pin "A9") (pinfunction "VDDIO_A9") (pintype "power_in"))
      (node (ref "U1") (pin "B1") (pinfunction "VDDIO_B1") (pintype "power_in"))
      (node (ref "U1") (pin "E10") (pinfunction "VDDIO_E10") (pintype "power_in"))
      (node (ref "U1") (pin "E13") (pinfunction "VDDIO_E13") (pintype "power_in"))
      (node (ref "U1") (pin "E16") (pinfunction "VDDIO_E16") (pintype "power_in"))
      (node (ref "U1") (pin "E7") (pinfunction "VDDIO_E7") (pintype "power_in"))
      (node (ref "U1") (pin "F10") (pinfunction "VDDIO_F10") (pintype "power_in"))
      (node (ref "U1") (pin "F13") (pinfunction "VDDIO_F13") (pintype "power_in"))
      (node (ref "U1") (pin "F16") (pinfunction "VDDIO_F16") (pintype "power_in"))
      (node (ref "U1") (pin "F7") (pinfunction "VDDIO_F7") (pintype "power_in"))
      (node (ref "U1") (pin "G5") (pinfunction "VDDIO_G5") (pintype "power_in"))
      (node (ref "U1") (pin "G6") (pinfunction "VDDIO_G6") (pintype "power_in"))
      (node (ref "U1") (pin "H5") (pinfunction "VDDIO_H5") (pintype "power_in"))
      (node (ref "U1") (pin "H6") (pinfunction "VDDIO_H6") (pintype "power_in"))
      (node (ref "U1") (pin "L14") (pinfunction "VDDIO_L14") (pintype "power_in"))
      (node (ref "U1") (pin "L15") (pinfunction "VDDIO_L15") (pintype "power_in"))
      (node (ref "U1") (pin "M1") (pinfunction "VDDIO_M1") (pintype "power_in"))
      (node (ref "U1") (pin "M5") (pinfunction "VDDIO_M5") (pintype "power_in"))
      (node (ref "U1") (pin "M6") (pinfunction "VDDIO_M6") (pintype "power_in"))
      (node (ref "U1") (pin "N14") (pinfunction "VDDIO_N14") (pintype "power_in"))
      (node (ref "U1") (pin "N15") (pinfunction "VDDIO_N15") (pintype "power_in"))
      (node (ref "U1") (pin "P9") (pinfunction "VDDIO_P9") (pintype "power_in"))
      (node (ref "U1") (pin "R9") (pinfunction "VDDIO_R9") (pintype "power_in"))
      (node (ref "U1") (pin "V19") (pinfunction "VDDIO_V19") (pintype "power_in"))
      (node (ref "U1") (pin "W8") (pinfunction "VDDIO_W8") (pintype "power_in"))
    )
  )
)
